# rrled.net
KiCad netlist of a schematic drawn in EAGLE
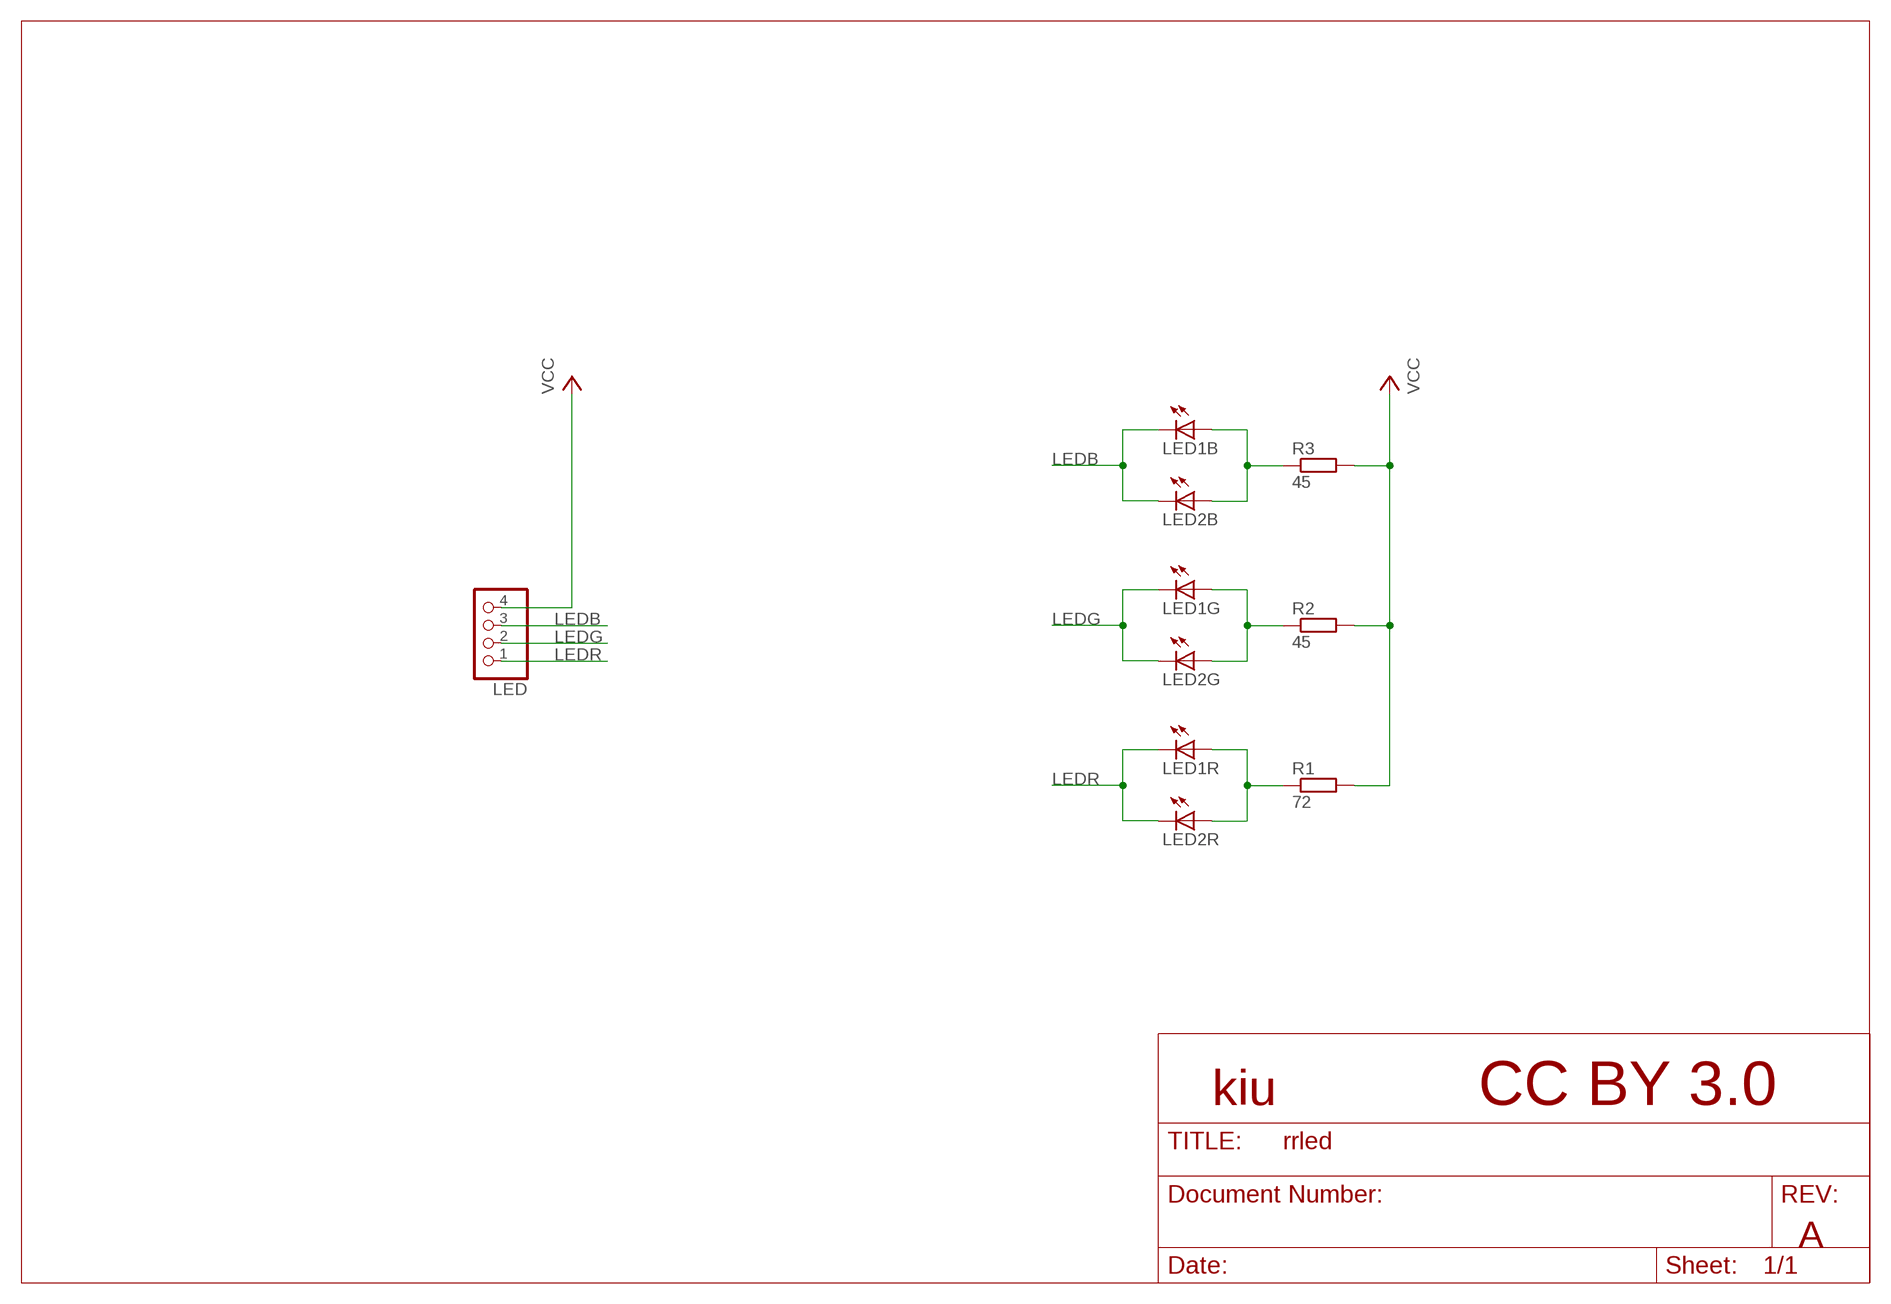
[diagram p0: schematic, sheet 1]

(export (version "E")
  (design (tool "Eeschema 10.0.6"))
  (components
    (comp (ref "LED")
      (value "PINHD-1X4")
      (footprint "eagle-import:1X04")
      (libsource (lib "eagle-import") (part "PINHD-1X4"))
    )
    (comp (ref "LED1")
      (value "MULTILED_LRTB_G6TG")
      (footprint "eagle-import:P-LCC-6_TOPLED")
      (libsource (lib "eagle-import") (part "MULTILED_LRTB_G6TG"))
    )
    (comp (ref "LED2")
      (value "MULTILED_LRTB_G6TG")
      (footprint "eagle-import:P-LCC-6_TOPLED")
      (libsource (lib "eagle-import") (part "MULTILED_LRTB_G6TG"))
    )
    (comp (ref "R1")
      (value "72")
      (footprint "eagle-import:R0603")
      (libsource (lib "eagle-import") (part "R-EU_R0603"))
    )
    (comp (ref "R2")
      (value "45")
      (footprint "eagle-import:R0603")
      (libsource (lib "eagle-import") (part "R-EU_R0603"))
    )
    (comp (ref "R3")
      (value "45")
      (footprint "eagle-import:R0603")
      (libsource (lib "eagle-import") (part "R-EU_R0603"))
    )
  )
  (nets
    (net (code "1") (name "/LEDB") (class "Default")
      (node (ref "LED") (pin "3") (pinfunction "3_3") (pintype "passive"))
      (node (ref "LED1") (pin "C3") (pinfunction "C_C3") (pintype "passive"))
      (node (ref "LED2") (pin "C3") (pinfunction "C_C3") (pintype "passive"))
    )
    (net (code "2") (name "/LEDG") (class "Default")
      (node (ref "LED") (pin "2") (pinfunction "2_2") (pintype "passive"))
      (node (ref "LED1") (pin "C2") (pinfunction "C_C2") (pintype "passive"))
      (node (ref "LED2") (pin "C2") (pinfunction "C_C2") (pintype "passive"))
    )
    (net (code "3") (name "/LEDR") (class "Default")
      (node (ref "LED") (pin "1") (pinfunction "1_1") (pintype "passive"))
      (node (ref "LED1") (pin "C1") (pinfunction "C_C1") (pintype "passive"))
      (node (ref "LED2") (pin "C1") (pinfunction "C_C1") (pintype "passive"))
    )
    (net (code "4") (name "Net-(LED1A-A)") (class "Default")
      (node (ref "LED1") (pin "A3") (pinfunction "A_A3") (pintype "passive"))
      (node (ref "LED2") (pin "A3") (pinfunction "A_A3") (pintype "passive"))
      (node (ref "R3") (pin "1") (pinfunction "1_1") (pintype "passive"))
    )
    (net (code "5") (name "Net-(LED1B-A)") (class "Default")
      (node (ref "LED1") (pin "A2") (pinfunction "A_A2") (pintype "passive"))
      (node (ref "LED2") (pin "A2") (pinfunction "A_A2") (pintype "passive"))
      (node (ref "R2") (pin "1") (pinfunction "1_1") (pintype "passive"))
    )
    (net (code "6") (name "Net-(LED1C-A)") (class "Default")
      (node (ref "LED1") (pin "A1") (pinfunction "A_A1") (pintype "passive"))
      (node (ref "LED2") (pin "A1") (pinfunction "A_A1") (pintype "passive"))
      (node (ref "R1") (pin "1") (pinfunction "1_1") (pintype "passive"))
    )
    (net (code "7") (name "VCC") (class "Default")
      (node (ref "LED") (pin "4") (pinfunction "4_4") (pintype "passive"))
      (node (ref "R1") (pin "2") (pinfunction "2_2") (pintype "passive"))
      (node (ref "R2") (pin "2") (pinfunction "2_2") (pintype "passive"))
      (node (ref "R3") (pin "2") (pinfunction "2_2") (pintype "passive"))
    )
  )
)
